# KeyMatrix.net
KiCad netlist of a schematic drawn in Altium Designer
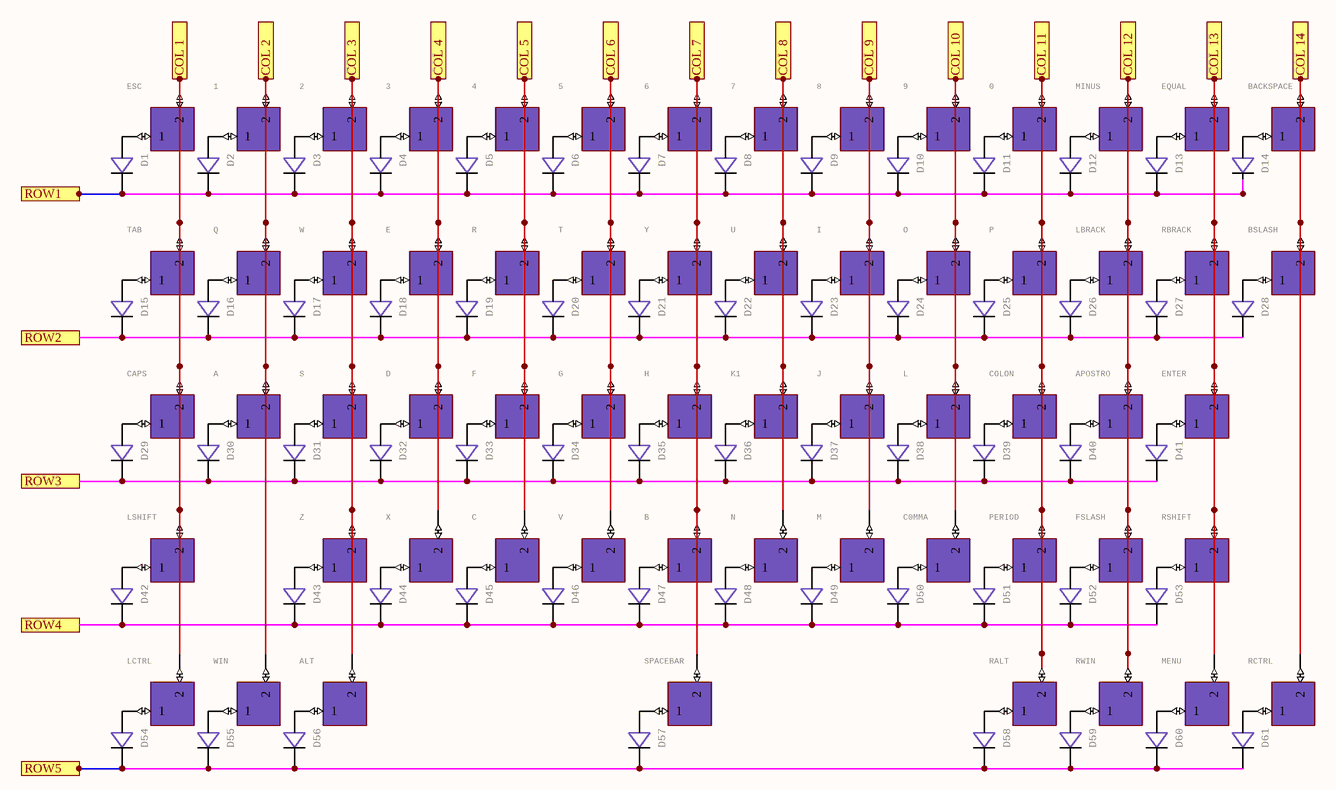
[diagram p0: KeyMatrix.SchDoc]

(export (version "E")
  (design (tool "Eeschema 10.0.6"))
  (components
    (comp (ref "0")
      (value "KEYSWITCH-PLAIN-MXHSPCB-1U")
      (footprint "MXHSPCB-1U")
      (libsource (lib "default_60") (part "KEYSWITCH-PLAIN-MXHSPCB-1U"))
    )
    (comp (ref "1")
      (value "KEYSWITCH-PLAIN-MXHSPCB-1U")
      (footprint "MXHSPCB-1U")
      (libsource (lib "default_60") (part "KEYSWITCH-PLAIN-MXHSPCB-1U"))
    )
    (comp (ref "2")
      (value "KEYSWITCH-PLAIN-MXHSPCB-1U")
      (footprint "MXHSPCB-1U")
      (libsource (lib "default_60") (part "KEYSWITCH-PLAIN-MXHSPCB-1U"))
    )
    (comp (ref "3")
      (value "KEYSWITCH-PLAIN-MXHSPCB-1U")
      (footprint "MXHSPCB-1U")
      (libsource (lib "default_60") (part "KEYSWITCH-PLAIN-MXHSPCB-1U"))
    )
    (comp (ref "4")
      (value "KEYSWITCH-PLAIN-MXHSPCB-1U")
      (footprint "MXHSPCB-1U")
      (libsource (lib "default_60") (part "KEYSWITCH-PLAIN-MXHSPCB-1U"))
    )
    (comp (ref "5")
      (value "KEYSWITCH-PLAIN-MXHSPCB-1U")
      (footprint "MXHSPCB-1U")
      (libsource (lib "default_60") (part "KEYSWITCH-PLAIN-MXHSPCB-1U"))
    )
    (comp (ref "6")
      (value "KEYSWITCH-PLAIN-MXHSPCB-1U")
      (footprint "MXHSPCB-1U")
      (libsource (lib "default_60") (part "KEYSWITCH-PLAIN-MXHSPCB-1U"))
    )
    (comp (ref "7")
      (value "KEYSWITCH-PLAIN-MXHSPCB-1U")
      (footprint "MXHSPCB-1U")
      (libsource (lib "default_60") (part "KEYSWITCH-PLAIN-MXHSPCB-1U"))
    )
    (comp (ref "8")
      (value "KEYSWITCH-PLAIN-MXHSPCB-1U")
      (footprint "MXHSPCB-1U")
      (libsource (lib "default_60") (part "KEYSWITCH-PLAIN-MXHSPCB-1U"))
    )
    (comp (ref "9")
      (value "KEYSWITCH-PLAIN-MXHSPCB-1U")
      (footprint "MXHSPCB-1U")
      (libsource (lib "default_60") (part "KEYSWITCH-PLAIN-MXHSPCB-1U"))
    )
    (comp (ref "A")
      (value "KEYSWITCH-PLAIN-MXHSPCB-1U")
      (footprint "MXHSPCB-1U")
      (libsource (lib "default_60") (part "KEYSWITCH-PLAIN-MXHSPCB-1U"))
    )
    (comp (ref "ALT")
      (value "KEYSWITCH-PLAIN-MXHSPCB-1U")
      (footprint "MXHSPCB-1U")
      (libsource (lib "default_60") (part "KEYSWITCH-PLAIN-MXHSPCB-1U"))
    )
    (comp (ref "APOSTRO")
      (value "KEYSWITCH-PLAIN-MXHSPCB-1U")
      (footprint "MXHSPCB-1U")
      (libsource (lib "default_60") (part "KEYSWITCH-PLAIN-MXHSPCB-1U"))
    )
    (comp (ref "B")
      (value "KEYSWITCH-PLAIN-MXHSPCB-1U")
      (footprint "MXHSPCB-1U")
      (libsource (lib "default_60") (part "KEYSWITCH-PLAIN-MXHSPCB-1U"))
    )
    (comp (ref "BACKSPACE")
      (value "KEYSWITCH-PLAIN-MXHSPCB-2U")
      (footprint "MXHSPCB-2U-LEDHOLE")
      (libsource (lib "default_60") (part "KEYSWITCH-PLAIN-MXHSPCB-2U"))
    )
    (comp (ref "BSLASH")
      (value "KEYSWITCH-PLAIN-MXHSPCB-1U")
      (footprint "MXHSPCB-1U")
      (libsource (lib "default_60") (part "KEYSWITCH-PLAIN-MXHSPCB-1U"))
    )
    (comp (ref "C")
      (value "KEYSWITCH-PLAIN-MXHSPCB-1U")
      (footprint "MXHSPCB-1U")
      (libsource (lib "default_60") (part "KEYSWITCH-PLAIN-MXHSPCB-1U"))
    )
    (comp (ref "C0MMA")
      (value "KEYSWITCH-PLAIN-MXHSPCB-1U")
      (footprint "MXHSPCB-1U")
      (libsource (lib "default_60") (part "KEYSWITCH-PLAIN-MXHSPCB-1U"))
    )
    (comp (ref "CAPS")
      (value "KEYSWITCH-PLAIN-MXHSPCB-1U")
      (footprint "MXHSPCB-1U")
      (libsource (lib "default_60") (part "KEYSWITCH-PLAIN-MXHSPCB-1U"))
    )
    (comp (ref "COLON")
      (value "KEYSWITCH-PLAIN-MXHSPCB-1U")
      (footprint "MXHSPCB-1U")
      (libsource (lib "default_60") (part "KEYSWITCH-PLAIN-MXHSPCB-1U"))
    )
    (comp (ref "D")
      (value "KEYSWITCH-PLAIN-MXHSPCB-1U")
      (footprint "MXHSPCB-1U")
      (libsource (lib "default_60") (part "KEYSWITCH-PLAIN-MXHSPCB-1U"))
    )
    (comp (ref "D1")
      (value "Standard 1N4148 diode")
      (footprint "SOD-123")
      (libsource (lib "default_60") (part "DIODE-SOD-123"))
    )
    (comp (ref "D2")
      (value "Standard 1N4148 diode")
      (footprint "SOD-123")
      (libsource (lib "default_60") (part "DIODE-SOD-123"))
    )
    (comp (ref "D3")
      (value "Standard 1N4148 diode")
      (footprint "SOD-123")
      (libsource (lib "default_60") (part "DIODE-SOD-123"))
    )
    (comp (ref "D4")
      (value "Standard 1N4148 diode")
      (footprint "SOD-123")
      (libsource (lib "default_60") (part "DIODE-SOD-123"))
    )
    (comp (ref "D5")
      (value "Standard 1N4148 diode")
      (footprint "SOD-123")
      (libsource (lib "default_60") (part "DIODE-SOD-123"))
    )
    (comp (ref "D6")
      (value "Standard 1N4148 diode")
      (footprint "SOD-123")
      (libsource (lib "default_60") (part "DIODE-SOD-123"))
    )
    (comp (ref "D7")
      (value "Standard 1N4148 diode")
      (footprint "SOD-123")
      (libsource (lib "default_60") (part "DIODE-SOD-123"))
    )
    (comp (ref "D8")
      (value "Standard 1N4148 diode")
      (footprint "SOD-123")
      (libsource (lib "default_60") (part "DIODE-SOD-123"))
    )
    (comp (ref "D9")
      (value "Standard 1N4148 diode")
      (footprint "SOD-123")
      (libsource (lib "default_60") (part "DIODE-SOD-123"))
    )
    (comp (ref "D10")
      (value "Standard 1N4148 diode")
      (footprint "SOD-123")
      (libsource (lib "default_60") (part "DIODE-SOD-123"))
    )
    (comp (ref "D11")
      (value "Standard 1N4148 diode")
      (footprint "SOD-123")
      (libsource (lib "default_60") (part "DIODE-SOD-123"))
    )
    (comp (ref "D12")
      (value "Standard 1N4148 diode")
      (footprint "SOD-123")
      (libsource (lib "default_60") (part "DIODE-SOD-123"))
    )
    (comp (ref "D13")
      (value "Standard 1N4148 diode")
      (footprint "SOD-123")
      (libsource (lib "default_60") (part "DIODE-SOD-123"))
    )
    (comp (ref "D14")
      (value "Standard 1N4148 diode")
      (footprint "SOD-123")
      (libsource (lib "default_60") (part "DIODE-SOD-123"))
    )
    (comp (ref "D15")
      (value "Standard 1N4148 diode")
      (footprint "SOD-123")
      (libsource (lib "default_60") (part "DIODE-SOD-123"))
    )
    (comp (ref "D16")
      (value "Standard 1N4148 diode")
      (footprint "SOD-123")
      (libsource (lib "default_60") (part "DIODE-SOD-123"))
    )
    (comp (ref "D17")
      (value "Standard 1N4148 diode")
      (footprint "SOD-123")
      (libsource (lib "default_60") (part "DIODE-SOD-123"))
    )
    (comp (ref "D18")
      (value "Standard 1N4148 diode")
      (footprint "SOD-123")
      (libsource (lib "default_60") (part "DIODE-SOD-123"))
    )
    (comp (ref "D19")
      (value "Standard 1N4148 diode")
      (footprint "SOD-123")
      (libsource (lib "default_60") (part "DIODE-SOD-123"))
    )
    (comp (ref "D20")
      (value "Standard 1N4148 diode")
      (footprint "SOD-123")
      (libsource (lib "default_60") (part "DIODE-SOD-123"))
    )
    (comp (ref "D21")
      (value "Standard 1N4148 diode")
      (footprint "SOD-123")
      (libsource (lib "default_60") (part "DIODE-SOD-123"))
    )
    (comp (ref "D22")
      (value "Standard 1N4148 diode")
      (footprint "SOD-123")
      (libsource (lib "default_60") (part "DIODE-SOD-123"))
    )
    (comp (ref "D23")
      (value "Standard 1N4148 diode")
      (footprint "SOD-123")
      (libsource (lib "default_60") (part "DIODE-SOD-123"))
    )
    (comp (ref "D24")
      (value "Standard 1N4148 diode")
      (footprint "SOD-123")
      (libsource (lib "default_60") (part "DIODE-SOD-123"))
    )
    (comp (ref "D25")
      (value "Standard 1N4148 diode")
      (footprint "SOD-123")
      (libsource (lib "default_60") (part "DIODE-SOD-123"))
    )
    (comp (ref "D26")
      (value "Standard 1N4148 diode")
      (footprint "SOD-123")
      (libsource (lib "default_60") (part "DIODE-SOD-123"))
    )
    (comp (ref "D27")
      (value "Standard 1N4148 diode")
      (footprint "SOD-123")
      (libsource (lib "default_60") (part "DIODE-SOD-123"))
    )
    (comp (ref "D28")
      (value "Standard 1N4148 diode")
      (footprint "SOD-123")
      (libsource (lib "default_60") (part "DIODE-SOD-123"))
    )
    (comp (ref "D29")
      (value "Standard 1N4148 diode")
      (footprint "SOD-123")
      (libsource (lib "default_60") (part "DIODE-SOD-123"))
    )
    (comp (ref "D30")
      (value "Standard 1N4148 diode")
      (footprint "SOD-123")
      (libsource (lib "default_60") (part "DIODE-SOD-123"))
    )
    (comp (ref "D31")
      (value "Standard 1N4148 diode")
      (footprint "SOD-123")
      (libsource (lib "default_60") (part "DIODE-SOD-123"))
    )
    (comp (ref "D32")
      (value "Standard 1N4148 diode")
      (footprint "SOD-123")
      (libsource (lib "default_60") (part "DIODE-SOD-123"))
    )
    (comp (ref "D33")
      (value "Standard 1N4148 diode")
      (footprint "SOD-123")
      (libsource (lib "default_60") (part "DIODE-SOD-123"))
    )
    (comp (ref "D34")
      (value "Standard 1N4148 diode")
      (footprint "SOD-123")
      (libsource (lib "default_60") (part "DIODE-SOD-123"))
    )
    (comp (ref "D35")
      (value "Standard 1N4148 diode")
      (footprint "SOD-123")
      (libsource (lib "default_60") (part "DIODE-SOD-123"))
    )
    (comp (ref "D36")
      (value "Standard 1N4148 diode")
      (footprint "SOD-123")
      (libsource (lib "default_60") (part "DIODE-SOD-123"))
    )
    (comp (ref "D37")
      (value "Standard 1N4148 diode")
      (footprint "SOD-123")
      (libsource (lib "default_60") (part "DIODE-SOD-123"))
    )
    (comp (ref "D38")
      (value "Standard 1N4148 diode")
      (footprint "SOD-123")
      (libsource (lib "default_60") (part "DIODE-SOD-123"))
    )
    (comp (ref "D39")
      (value "Standard 1N4148 diode")
      (footprint "SOD-123")
      (libsource (lib "default_60") (part "DIODE-SOD-123"))
    )
    (comp (ref "D40")
      (value "Standard 1N4148 diode")
      (footprint "SOD-123")
      (libsource (lib "default_60") (part "DIODE-SOD-123"))
    )
    (comp (ref "D41")
      (value "Standard 1N4148 diode")
      (footprint "SOD-123")
      (libsource (lib "default_60") (part "DIODE-SOD-123"))
    )
    (comp (ref "D42")
      (value "Standard 1N4148 diode")
      (footprint "SOD-123")
      (libsource (lib "default_60") (part "DIODE-SOD-123"))
    )
    (comp (ref "D43")
      (value "Standard 1N4148 diode")
      (footprint "SOD-123")
      (libsource (lib "default_60") (part "DIODE-SOD-123"))
    )
    (comp (ref "D44")
      (value "Standard 1N4148 diode")
      (footprint "SOD-123")
      (libsource (lib "default_60") (part "DIODE-SOD-123"))
    )
    (comp (ref "D45")
      (value "Standard 1N4148 diode")
      (footprint "SOD-123")
      (libsource (lib "default_60") (part "DIODE-SOD-123"))
    )
    (comp (ref "D46")
      (value "Standard 1N4148 diode")
      (footprint "SOD-123")
      (libsource (lib "default_60") (part "DIODE-SOD-123"))
    )
    (comp (ref "D47")
      (value "Standard 1N4148 diode")
      (footprint "SOD-123")
      (libsource (lib "default_60") (part "DIODE-SOD-123"))
    )
    (comp (ref "D48")
      (value "Standard 1N4148 diode")
      (footprint "SOD-123")
      (libsource (lib "default_60") (part "DIODE-SOD-123"))
    )
    (comp (ref "D49")
      (value "Standard 1N4148 diode")
      (footprint "SOD-123")
      (libsource (lib "default_60") (part "DIODE-SOD-123"))
    )
    (comp (ref "D50")
      (value "Standard 1N4148 diode")
      (footprint "SOD-123")
      (libsource (lib "default_60") (part "DIODE-SOD-123"))
    )
    (comp (ref "D51")
      (value "Standard 1N4148 diode")
      (footprint "SOD-123")
      (libsource (lib "default_60") (part "DIODE-SOD-123"))
    )
    (comp (ref "D52")
      (value "Standard 1N4148 diode")
      (footprint "SOD-123")
      (libsource (lib "default_60") (part "DIODE-SOD-123"))
    )
    (comp (ref "D53")
      (value "Standard 1N4148 diode")
      (footprint "SOD-123")
      (libsource (lib "default_60") (part "DIODE-SOD-123"))
    )
    (comp (ref "D54")
      (value "Standard 1N4148 diode")
      (footprint "SOD-123")
      (libsource (lib "default_60") (part "DIODE-SOD-123"))
    )
    (comp (ref "D55")
      (value "Standard 1N4148 diode")
      (footprint "SOD-123")
      (libsource (lib "default_60") (part "DIODE-SOD-123"))
    )
    (comp (ref "D56")
      (value "Standard 1N4148 diode")
      (footprint "SOD-123")
      (libsource (lib "default_60") (part "DIODE-SOD-123"))
    )
    (comp (ref "D57")
      (value "Standard 1N4148 diode")
      (footprint "SOD-123")
      (libsource (lib "default_60") (part "DIODE-SOD-123"))
    )
    (comp (ref "D58")
      (value "Standard 1N4148 diode")
      (footprint "SOD-123")
      (libsource (lib "default_60") (part "DIODE-SOD-123"))
    )
    (comp (ref "D59")
      (value "Standard 1N4148 diode")
      (footprint "SOD-123")
      (libsource (lib "default_60") (part "DIODE-SOD-123"))
    )
    (comp (ref "D60")
      (value "Standard 1N4148 diode")
      (footprint "SOD-123")
      (libsource (lib "default_60") (part "DIODE-SOD-123"))
    )
    (comp (ref "D61")
      (value "Standard 1N4148 diode")
      (footprint "SOD-123")
      (libsource (lib "default_60") (part "DIODE-SOD-123"))
    )
    (comp (ref "E")
      (value "KEYSWITCH-PLAIN-MXHSPCB-1U")
      (footprint "MXHSPCB-1U")
      (libsource (lib "default_60") (part "KEYSWITCH-PLAIN-MXHSPCB-1U"))
    )
    (comp (ref "ENTER")
      (value "KEYSWITCH-PLAIN-MXHSPCB-2U")
      (footprint "MXHSPCB-2U-LEDHOLE")
      (libsource (lib "default_60") (part "KEYSWITCH-PLAIN-MXHSPCB-2U"))
    )
    (comp (ref "EQUAL")
      (value "KEYSWITCH-PLAIN-MXHSPCB-1U")
      (footprint "MXHSPCB-1U")
      (libsource (lib "default_60") (part "KEYSWITCH-PLAIN-MXHSPCB-1U"))
    )
    (comp (ref "ESC")
      (value "KEYSWITCH-PLAIN-MXHSPCB-1U")
      (footprint "MXHSPCB-1U")
      (libsource (lib "default_60") (part "KEYSWITCH-PLAIN-MXHSPCB-1U"))
    )
    (comp (ref "F")
      (value "KEYSWITCH-PLAIN-MXHSPCB-1U")
      (footprint "MXHSPCB-1U")
      (libsource (lib "default_60") (part "KEYSWITCH-PLAIN-MXHSPCB-1U"))
    )
    (comp (ref "FSLASH")
      (value "KEYSWITCH-PLAIN-MXHSPCB-1U")
      (footprint "MXHSPCB-1U")
      (libsource (lib "default_60") (part "KEYSWITCH-PLAIN-MXHSPCB-1U"))
    )
    (comp (ref "G")
      (value "KEYSWITCH-PLAIN-MXHSPCB-1U")
      (footprint "MXHSPCB-1U")
      (libsource (lib "default_60") (part "KEYSWITCH-PLAIN-MXHSPCB-1U"))
    )
    (comp (ref "H")
      (value "KEYSWITCH-PLAIN-MXHSPCB-1U")
      (footprint "MXHSPCB-1U")
      (libsource (lib "default_60") (part "KEYSWITCH-PLAIN-MXHSPCB-1U"))
    )
    (comp (ref "I")
      (value "KEYSWITCH-PLAIN-MXHSPCB-1U")
      (footprint "MXHSPCB-1U")
      (libsource (lib "default_60") (part "KEYSWITCH-PLAIN-MXHSPCB-1U"))
    )
    (comp (ref "J")
      (value "KEYSWITCH-PLAIN-MXHSPCB-1U")
      (footprint "MXHSPCB-1U")
      (libsource (lib "default_60") (part "KEYSWITCH-PLAIN-MXHSPCB-1U"))
    )
    (comp (ref "K1")
      (value "KEYSWITCH-PLAIN-MXHSPCB-1U")
      (footprint "MXHSPCB-1U")
      (libsource (lib "default_60") (part "KEYSWITCH-PLAIN-MXHSPCB-1U"))
    )
    (comp (ref "L")
      (value "KEYSWITCH-PLAIN-MXHSPCB-1U")
      (footprint "MXHSPCB-1U")
      (libsource (lib "default_60") (part "KEYSWITCH-PLAIN-MXHSPCB-1U"))
    )
    (comp (ref "LBRACK")
      (value "KEYSWITCH-PLAIN-MXHSPCB-1U")
      (footprint "MXHSPCB-1U")
      (libsource (lib "default_60") (part "KEYSWITCH-PLAIN-MXHSPCB-1U"))
    )
    (comp (ref "LCTRL")
      (value "KEYSWITCH-PLAIN-MXHSPCB-1U")
      (footprint "MXHSPCB-1U")
      (libsource (lib "default_60") (part "KEYSWITCH-PLAIN-MXHSPCB-1U"))
    )
    (comp (ref "LSHIFT")
      (value "KEYSWITCH-PLAIN-MXHSPCB-2U")
      (footprint "MXHSPCB-2U-LEDHOLE")
      (libsource (lib "default_60") (part "KEYSWITCH-PLAIN-MXHSPCB-2U"))
    )
    (comp (ref "M")
      (value "KEYSWITCH-PLAIN-MXHSPCB-1U")
      (footprint "MXHSPCB-1U")
      (libsource (lib "default_60") (part "KEYSWITCH-PLAIN-MXHSPCB-1U"))
    )
    (comp (ref "MENU")
      (value "KEYSWITCH-PLAIN-MXHSPCB-1U")
      (footprint "MXHSPCB-1U")
      (libsource (lib "default_60") (part "KEYSWITCH-PLAIN-MXHSPCB-1U"))
    )
    (comp (ref "MINUS")
      (value "KEYSWITCH-PLAIN-MXHSPCB-1U")
      (footprint "MXHSPCB-1U")
      (libsource (lib "default_60") (part "KEYSWITCH-PLAIN-MXHSPCB-1U"))
    )
    (comp (ref "N")
      (value "KEYSWITCH-PLAIN-MXHSPCB-1U")
      (footprint "MXHSPCB-1U")
      (libsource (lib "default_60") (part "KEYSWITCH-PLAIN-MXHSPCB-1U"))
    )
    (comp (ref "O")
      (value "KEYSWITCH-PLAIN-MXHSPCB-1U")
      (footprint "MXHSPCB-1U")
      (libsource (lib "default_60") (part "KEYSWITCH-PLAIN-MXHSPCB-1U"))
    )
    (comp (ref "P")
      (value "KEYSWITCH-PLAIN-MXHSPCB-1U")
      (footprint "MXHSPCB-1U")
      (libsource (lib "default_60") (part "KEYSWITCH-PLAIN-MXHSPCB-1U"))
    )
    (comp (ref "PERIOD")
      (value "KEYSWITCH-PLAIN-MXHSPCB-1U")
      (footprint "MXHSPCB-1U")
      (libsource (lib "default_60") (part "KEYSWITCH-PLAIN-MXHSPCB-1U"))
    )
    (comp (ref "Q")
      (value "KEYSWITCH-PLAIN-MXHSPCB-1U")
      (footprint "MXHSPCB-1U")
      (libsource (lib "default_60") (part "KEYSWITCH-PLAIN-MXHSPCB-1U"))
    )
    (comp (ref "R")
      (value "KEYSWITCH-PLAIN-MXHSPCB-1U")
      (footprint "MXHSPCB-1U")
      (libsource (lib "default_60") (part "KEYSWITCH-PLAIN-MXHSPCB-1U"))
    )
    (comp (ref "RALT")
      (value "KEYSWITCH-PLAIN-MXHSPCB-1U")
      (footprint "MXHSPCB-1U")
      (libsource (lib "default_60") (part "KEYSWITCH-PLAIN-MXHSPCB-1U"))
    )
    (comp (ref "RBRACK")
      (value "KEYSWITCH-PLAIN-MXHSPCB-1U")
      (footprint "MXHSPCB-1U")
      (libsource (lib "default_60") (part "KEYSWITCH-PLAIN-MXHSPCB-1U"))
    )
    (comp (ref "RCTRL")
      (value "KEYSWITCH-PLAIN-MXHSPCB-1U")
      (footprint "MXHSPCB-1U")
      (libsource (lib "default_60") (part "KEYSWITCH-PLAIN-MXHSPCB-1U"))
    )
    (comp (ref "RSHIFT")
      (value "KEYSWITCH-PLAIN-MXHSPCB-2U")
      (footprint "MXHSPCB-2U-LEDHOLE")
      (libsource (lib "default_60") (part "KEYSWITCH-PLAIN-MXHSPCB-2U"))
    )
    (comp (ref "RWIN")
      (value "KEYSWITCH-PLAIN-MXHSPCB-1U")
      (footprint "MXHSPCB-1U")
      (libsource (lib "default_60") (part "KEYSWITCH-PLAIN-MXHSPCB-1U"))
    )
    (comp (ref "S")
      (value "KEYSWITCH-PLAIN-MXHSPCB-1U")
      (footprint "MXHSPCB-1U")
      (libsource (lib "default_60") (part "KEYSWITCH-PLAIN-MXHSPCB-1U"))
    )
    (comp (ref "SPACEBAR")
      (value "KEYSWITCH-PLAIN-MXHSPCB-6.25U")
      (footprint "MXHSPCB-6.25U-FLIPPED")
      (libsource (lib "default_60") (part "KEYSWITCH-PLAIN-MXHSPCB-6.25U"))
    )
    (comp (ref "T")
      (value "KEYSWITCH-PLAIN-MXHSPCB-1U")
      (footprint "MXHSPCB-1U")
      (libsource (lib "default_60") (part "KEYSWITCH-PLAIN-MXHSPCB-1U"))
    )
    (comp (ref "TAB")
      (value "KEYSWITCH-PLAIN-MXHSPCB-1U")
      (footprint "MXHSPCB-1U")
      (libsource (lib "default_60") (part "KEYSWITCH-PLAIN-MXHSPCB-1U"))
    )
    (comp (ref "U")
      (value "KEYSWITCH-PLAIN-MXHSPCB-1U")
      (footprint "MXHSPCB-1U")
      (libsource (lib "default_60") (part "KEYSWITCH-PLAIN-MXHSPCB-1U"))
    )
    (comp (ref "V")
      (value "KEYSWITCH-PLAIN-MXHSPCB-1U")
      (footprint "MXHSPCB-1U")
      (libsource (lib "default_60") (part "KEYSWITCH-PLAIN-MXHSPCB-1U"))
    )
    (comp (ref "W")
      (value "KEYSWITCH-PLAIN-MXHSPCB-1U")
      (footprint "MXHSPCB-1U")
      (libsource (lib "default_60") (part "KEYSWITCH-PLAIN-MXHSPCB-1U"))
    )
    (comp (ref "WIN")
      (value "KEYSWITCH-PLAIN-MXHSPCB-1U")
      (footprint "MXHSPCB-1U")
      (libsource (lib "default_60") (part "KEYSWITCH-PLAIN-MXHSPCB-1U"))
    )
    (comp (ref "X")
      (value "KEYSWITCH-PLAIN-MXHSPCB-1U")
      (footprint "MXHSPCB-1U")
      (libsource (lib "default_60") (part "KEYSWITCH-PLAIN-MXHSPCB-1U"))
    )
    (comp (ref "Y")
      (value "KEYSWITCH-PLAIN-MXHSPCB-1U")
      (footprint "MXHSPCB-1U")
      (libsource (lib "default_60") (part "KEYSWITCH-PLAIN-MXHSPCB-1U"))
    )
    (comp (ref "Z")
      (value "KEYSWITCH-PLAIN-MXHSPCB-1U")
      (footprint "MXHSPCB-1U")
      (libsource (lib "default_60") (part "KEYSWITCH-PLAIN-MXHSPCB-1U"))
    )
  )
  (nets
    (net (code "1") (name "/COL 1") (class "Default")
      (node (ref "CAPS") (pin "MX2") (pinfunction "2_MX2") (pintype "bidirectional"))
      (node (ref "ESC") (pin "MX2") (pinfunction "2_MX2") (pintype "bidirectional"))
      (node (ref "LCTRL") (pin "MX2") (pinfunction "2_MX2") (pintype "bidirectional"))
      (node (ref "LSHIFT") (pin "MX2") (pinfunction "2_MX2") (pintype "bidirectional"))
      (node (ref "TAB") (pin "MX2") (pinfunction "2_MX2") (pintype "bidirectional"))
    )
    (net (code "2") (name "/COL 2") (class "Default")
      (node (ref "1") (pin "MX2") (pinfunction "2_MX2") (pintype "bidirectional"))
      (node (ref "A") (pin "MX2") (pinfunction "2_MX2") (pintype "bidirectional"))
      (node (ref "Q") (pin "MX2") (pinfunction "2_MX2") (pintype "bidirectional"))
      (node (ref "WIN") (pin "MX2") (pinfunction "2_MX2") (pintype "bidirectional"))
    )
    (net (code "3") (name "/COL 3") (class "Default")
      (node (ref "2") (pin "MX2") (pinfunction "2_MX2") (pintype "bidirectional"))
      (node (ref "ALT") (pin "MX2") (pinfunction "2_MX2") (pintype "bidirectional"))
      (node (ref "S") (pin "MX2") (pinfunction "2_MX2") (pintype "bidirectional"))
      (node (ref "W") (pin "MX2") (pinfunction "2_MX2") (pintype "bidirectional"))
      (node (ref "Z") (pin "MX2") (pinfunction "2_MX2") (pintype "bidirectional"))
    )
    (net (code "4") (name "/COL 4") (class "Default")
      (node (ref "3") (pin "MX2") (pinfunction "2_MX2") (pintype "bidirectional"))
      (node (ref "D") (pin "MX2") (pinfunction "2_MX2") (pintype "bidirectional"))
      (node (ref "E") (pin "MX2") (pinfunction "2_MX2") (pintype "bidirectional"))
      (node (ref "X") (pin "MX2") (pinfunction "2_MX2") (pintype "bidirectional"))
    )
    (net (code "5") (name "/COL 5") (class "Default")
      (node (ref "4") (pin "MX2") (pinfunction "2_MX2") (pintype "bidirectional"))
      (node (ref "C") (pin "MX2") (pinfunction "2_MX2") (pintype "bidirectional"))
      (node (ref "F") (pin "MX2") (pinfunction "2_MX2") (pintype "bidirectional"))
      (node (ref "R") (pin "MX2") (pinfunction "2_MX2") (pintype "bidirectional"))
    )
    (net (code "6") (name "/COL 6") (class "Default")
      (node (ref "5") (pin "MX2") (pinfunction "2_MX2") (pintype "bidirectional"))
      (node (ref "G") (pin "MX2") (pinfunction "2_MX2") (pintype "bidirectional"))
      (node (ref "T") (pin "MX2") (pinfunction "2_MX2") (pintype "bidirectional"))
      (node (ref "V") (pin "MX2") (pinfunction "2_MX2") (pintype "bidirectional"))
    )
    (net (code "7") (name "/COL 7") (class "Default")
      (node (ref "6") (pin "MX2") (pinfunction "2_MX2") (pintype "bidirectional"))
      (node (ref "B") (pin "MX2") (pinfunction "2_MX2") (pintype "bidirectional"))
      (node (ref "H") (pin "MX2") (pinfunction "2_MX2") (pintype "bidirectional"))
      (node (ref "SPACEBAR") (pin "MX2") (pinfunction "2_MX2") (pintype "bidirectional"))
      (node (ref "Y") (pin "MX2") (pinfunction "2_MX2") (pintype "bidirectional"))
    )
    (net (code "8") (name "/COL 8") (class "Default")
      (node (ref "7") (pin "MX2") (pinfunction "2_MX2") (pintype "bidirectional"))
      (node (ref "K1") (pin "MX2") (pinfunction "2_MX2") (pintype "bidirectional"))
      (node (ref "N") (pin "MX2") (pinfunction "2_MX2") (pintype "bidirectional"))
      (node (ref "U") (pin "MX2") (pinfunction "2_MX2") (pintype "bidirectional"))
    )
    (net (code "9") (name "/COL 9") (class "Default")
      (node (ref "8") (pin "MX2") (pinfunction "2_MX2") (pintype "bidirectional"))
      (node (ref "I") (pin "MX2") (pinfunction "2_MX2") (pintype "bidirectional"))
      (node (ref "J") (pin "MX2") (pinfunction "2_MX2") (pintype "bidirectional"))
      (node (ref "M") (pin "MX2") (pinfunction "2_MX2") (pintype "bidirectional"))
    )
    (net (code "10") (name "/COL 10") (class "Default")
      (node (ref "9") (pin "MX2") (pinfunction "2_MX2") (pintype "bidirectional"))
      (node (ref "C0MMA") (pin "MX2") (pinfunction "2_MX2") (pintype "bidirectional"))
      (node (ref "L") (pin "MX2") (pinfunction "2_MX2") (pintype "bidirectional"))
      (node (ref "O") (pin "MX2") (pinfunction "2_MX2") (pintype "bidirectional"))
    )
    (net (code "11") (name "/COL 11") (class "Default")
      (node (ref "0") (pin "MX2") (pinfunction "2_MX2") (pintype "bidirectional"))
      (node (ref "COLON") (pin "MX2") (pinfunction "2_MX2") (pintype "bidirectional"))
      (node (ref "P") (pin "MX2") (pinfunction "2_MX2") (pintype "bidirectional"))
      (node (ref "PERIOD") (pin "MX2") (pinfunction "2_MX2") (pintype "bidirectional"))
      (node (ref "RALT") (pin "MX2") (pinfunction "2_MX2") (pintype "bidirectional"))
    )
    (net (code "12") (name "/COL 12") (class "Default")
      (node (ref "APOSTRO") (pin "MX2") (pinfunction "2_MX2") (pintype "bidirectional"))
      (node (ref "FSLASH") (pin "MX2") (pinfunction "2_MX2") (pintype "bidirectional"))
      (node (ref "LBRACK") (pin "MX2") (pinfunction "2_MX2") (pintype "bidirectional"))
      (node (ref "MINUS") (pin "MX2") (pinfunction "2_MX2") (pintype "bidirectional"))
      (node (ref "RWIN") (pin "MX2") (pinfunction "2_MX2") (pintype "bidirectional"))
    )
    (net (code "13") (name "/COL 13") (class "Default")
      (node (ref "ENTER") (pin "MX2") (pinfunction "2_MX2") (pintype "bidirectional"))
      (node (ref "EQUAL") (pin "MX2") (pinfunction "2_MX2") (pintype "bidirectional"))
      (node (ref "MENU") (pin "MX2") (pinfunction "2_MX2") (pintype "bidirectional"))
      (node (ref "RBRACK") (pin "MX2") (pinfunction "2_MX2") (pintype "bidirectional"))
      (node (ref "RSHIFT") (pin "MX2") (pinfunction "2_MX2") (pintype "bidirectional"))
    )
    (net (code "14") (name "/COL 14") (class "Default")
      (node (ref "BACKSPACE") (pin "MX2") (pinfunction "2_MX2") (pintype "bidirectional"))
      (node (ref "BSLASH") (pin "MX2") (pinfunction "2_MX2") (pintype "bidirectional"))
      (node (ref "RCTRL") (pin "MX2") (pinfunction "2_MX2") (pintype "bidirectional"))
    )
    (net (code "15") (name "/ROW1") (class "Default")
      (node (ref "D1") (pin "C") (pinfunction "C_C") (pintype "passive"))
      (node (ref "D10") (pin "C") (pinfunction "C_C") (pintype "passive"))
      (node (ref "D11") (pin "C") (pinfunction "C_C") (pintype "passive"))
      (node (ref "D12") (pin "C") (pinfunction "C_C") (pintype "passive"))
      (node (ref "D13") (pin "C") (pinfunction "C_C") (pintype "passive"))
      (node (ref "D14") (pin "C") (pinfunction "C_C") (pintype "passive"))
      (node (ref "D2") (pin "C") (pinfunction "C_C") (pintype "passive"))
      (node (ref "D3") (pin "C") (pinfunction "C_C") (pintype "passive"))
      (node (ref "D4") (pin "C") (pinfunction "C_C") (pintype "passive"))
      (node (ref "D5") (pin "C") (pinfunction "C_C") (pintype "passive"))
      (node (ref "D6") (pin "C") (pinfunction "C_C") (pintype "passive"))
      (node (ref "D7") (pin "C") (pinfunction "C_C") (pintype "passive"))
      (node (ref "D8") (pin "C") (pinfunction "C_C") (pintype "passive"))
      (node (ref "D9") (pin "C") (pinfunction "C_C") (pintype "passive"))
    )
    (net (code "16") (name "/ROW2") (class "Default")
      (node (ref "D15") (pin "C") (pinfunction "C_C") (pintype "passive"))
      (node (ref "D16") (pin "C") (pinfunction "C_C") (pintype "passive"))
      (node (ref "D17") (pin "C") (pinfunction "C_C") (pintype "passive"))
      (node (ref "D18") (pin "C") (pinfunction "C_C") (pintype "passive"))
      (node (ref "D19") (pin "C") (pinfunction "C_C") (pintype "passive"))
      (node (ref "D20") (pin "C") (pinfunction "C_C") (pintype "passive"))
      (node (ref "D21") (pin "C") (pinfunction "C_C") (pintype "passive"))
      (node (ref "D22") (pin "C") (pinfunction "C_C") (pintype "passive"))
      (node (ref "D23") (pin "C") (pinfunction "C_C") (pintype "passive"))
      (node (ref "D24") (pin "C") (pinfunction "C_C") (pintype "passive"))
      (node (ref "D25") (pin "C") (pinfunction "C_C") (pintype "passive"))
      (node (ref "D26") (pin "C") (pinfunction "C_C") (pintype "passive"))
      (node (ref "D27") (pin "C") (pinfunction "C_C") (pintype "passive"))
      (node (ref "D28") (pin "C") (pinfunction "C_C") (pintype "passive"))
    )
    (net (code "17") (name "/ROW3") (class "Default")
      (node (ref "D29") (pin "C") (pinfunction "C_C") (pintype "passive"))
      (node (ref "D30") (pin "C") (pinfunction "C_C") (pintype "passive"))
      (node (ref "D31") (pin "C") (pinfunction "C_C") (pintype "passive"))
      (node (ref "D32") (pin "C") (pinfunction "C_C") (pintype "passive"))
      (node (ref "D33") (pin "C") (pinfunction "C_C") (pintype "passive"))
      (node (ref "D34") (pin "C") (pinfunction "C_C") (pintype "passive"))
      (node (ref "D35") (pin "C") (pinfunction "C_C") (pintype "passive"))
      (node (ref "D36") (pin "C") (pinfunction "C_C") (pintype "passive"))
      (node (ref "D37") (pin "C") (pinfunction "C_C") (pintype "passive"))
      (node (ref "D38") (pin "C") (pinfunction "C_C") (pintype "passive"))
      (node (ref "D39") (pin "C") (pinfunction "C_C") (pintype "passive"))
      (node (ref "D40") (pin "C") (pinfunction "C_C") (pintype "passive"))
      (node (ref "D41") (pin "C") (pinfunction "C_C") (pintype "passive"))
    )
    (net (code "18") (name "/ROW4") (class "Default")
      (node (ref "D42") (pin "C") (pinfunction "C_C") (pintype "passive"))
      (node (ref "D43") (pin "C") (pinfunction "C_C") (pintype "passive"))
      (node (ref "D44") (pin "C") (pinfunction "C_C") (pintype "passive"))
      (node (ref "D45") (pin "C") (pinfunction "C_C") (pintype "passive"))
      (node (ref "D46") (pin "C") (pinfunction "C_C") (pintype "passive"))
      (node (ref "D47") (pin "C") (pinfunction "C_C") (pintype "passive"))
      (node (ref "D48") (pin "C") (pinfunction "C_C") (pintype "passive"))
      (node (ref "D49") (pin "C") (pinfunction "C_C") (pintype "passive"))
      (node (ref "D50") (pin "C") (pinfunction "C_C") (pintype "passive"))
      (node (ref "D51") (pin "C") (pinfunction "C_C") (pintype "passive"))
      (node (ref "D52") (pin "C") (pinfunction "C_C") (pintype "passive"))
      (node (ref "D53") (pin "C") (pinfunction "C_C") (pintype "passive"))
    )
    (net (code "19") (name "/ROW5") (class "Default")
      (node (ref "D54") (pin "C") (pinfunction "C_C") (pintype "passive"))
      (node (ref "D55") (pin "C") (pinfunction "C_C") (pintype "passive"))
      (node (ref "D56") (pin "C") (pinfunction "C_C") (pintype "passive"))
      (node (ref "D57") (pin "C") (pinfunction "C_C") (pintype "passive"))
      (node (ref "D58") (pin "C") (pinfunction "C_C") (pintype "passive"))
      (node (ref "D59") (pin "C") (pinfunction "C_C") (pintype "passive"))
      (node (ref "D60") (pin "C") (pinfunction "C_C") (pintype "passive"))
      (node (ref "D61") (pin "C") (pinfunction "C_C") (pintype "passive"))
    )
    (net (code "20") (name "Net-(0-1)") (class "Default")
      (node (ref "0") (pin "MX1") (pinfunction "1_MX1") (pintype "bidirectional"))
      (node (ref "D11") (pin "A") (pinfunction "A_A") (pintype "passive"))
    )
    (net (code "21") (name "Net-(1-1)") (class "Default")
      (node (ref "1") (pin "MX1") (pinfunction "1_MX1") (pintype "bidirectional"))
      (node (ref "D2") (pin "A") (pinfunction "A_A") (pintype "passive"))
    )
    (net (code "22") (name "Net-(2-1)") (class "Default")
      (node (ref "2") (pin "MX1") (pinfunction "1_MX1") (pintype "bidirectional"))
      (node (ref "D3") (pin "A") (pinfunction "A_A") (pintype "passive"))
    )
    (net (code "23") (name "Net-(3-1)") (class "Default")
      (node (ref "3") (pin "MX1") (pinfunction "1_MX1") (pintype "bidirectional"))
      (node (ref "D4") (pin "A") (pinfunction "A_A") (pintype "passive"))
    )
    (net (code "24") (name "Net-(4-1)") (class "Default")
      (node (ref "4") (pin "MX1") (pinfunction "1_MX1") (pintype "bidirectional"))
      (node (ref "D5") (pin "A") (pinfunction "A_A") (pintype "passive"))
    )
    (net (code "25") (name "Net-(5-1)") (class "Default")
      (node (ref "5") (pin "MX1") (pinfunction "1_MX1") (pintype "bidirectional"))
      (node (ref "D6") (pin "A") (pinfunction "A_A") (pintype "passive"))
    )
    (net (code "26") (name "Net-(6-1)") (class "Default")
      (node (ref "6") (pin "MX1") (pinfunction "1_MX1") (pintype "bidirectional"))
      (node (ref "D7") (pin "A") (pinfunction "A_A") (pintype "passive"))
    )
    (net (code "27") (name "Net-(7-1)") (class "Default")
      (node (ref "7") (pin "MX1") (pinfunction "1_MX1") (pintype "bidirectional"))
      (node (ref "D8") (pin "A") (pinfunction "A_A") (pintype "passive"))
    )
    (net (code "28") (name "Net-(8-1)") (class "Default")
      (node (ref "8") (pin "MX1") (pinfunction "1_MX1") (pintype "bidirectional"))
      (node (ref "D9") (pin "A") (pinfunction "A_A") (pintype "passive"))
    )
    (net (code "29") (name "Net-(9-1)") (class "Default")
      (node (ref "9") (pin "MX1") (pinfunction "1_MX1") (pintype "bidirectional"))
      (node (ref "D10") (pin "A") (pinfunction "A_A") (pintype "passive"))
    )
    (net (code "30") (name "Net-(A-1)") (class "Default")
      (node (ref "A") (pin "MX1") (pinfunction "1_MX1") (pintype "bidirectional"))
      (node (ref "D30") (pin "A") (pinfunction "A_A") (pintype "passive"))
    )
    (net (code "31") (name "Net-(ALT-1)") (class "Default")
      (node (ref "ALT") (pin "MX1") (pinfunction "1_MX1") (pintype "bidirectional"))
      (node (ref "D56") (pin "A") (pinfunction "A_A") (pintype "passive"))
    )
    (net (code "32") (name "Net-(APOSTRO-1)") (class "Default")
      (node (ref "APOSTRO") (pin "MX1") (pinfunction "1_MX1") (pintype "bidirectional"))
      (node (ref "D40") (pin "A") (pinfunction "A_A") (pintype "passive"))
    )
    (net (code "33") (name "Net-(B-1)") (class "Default")
      (node (ref "B") (pin "MX1") (pinfunction "1_MX1") (pintype "bidirectional"))
      (node (ref "D47") (pin "A") (pinfunction "A_A") (pintype "passive"))
    )
    (net (code "34") (name "Net-(BACKSPACE-1)") (class "Default")
      (node (ref "BACKSPACE") (pin "MX1") (pinfunction "1_MX1") (pintype "bidirectional"))
      (node (ref "D14") (pin "A") (pinfunction "A_A") (pintype "passive"))
    )
    (net (code "35") (name "Net-(BSLASH-1)") (class "Default")
      (node (ref "BSLASH") (pin "MX1") (pinfunction "1_MX1") (pintype "bidirectional"))
      (node (ref "D28") (pin "A") (pinfunction "A_A") (pintype "passive"))
    )
    (net (code "36") (name "Net-(C-1)") (class "Default")
      (node (ref "C") (pin "MX1") (pinfunction "1_MX1") (pintype "bidirectional"))
      (node (ref "D45") (pin "A") (pinfunction "A_A") (pintype "passive"))
    )
    (net (code "37") (name "Net-(C0MMA-1)") (class "Default")
      (node (ref "C0MMA") (pin "MX1") (pinfunction "1_MX1") (pintype "bidirectional"))
      (node (ref "D50") (pin "A") (pinfunction "A_A") (pintype "passive"))
    )
    (net (code "38") (name "Net-(CAPS-1)") (class "Default")
      (node (ref "CAPS") (pin "MX1") (pinfunction "1_MX1") (pintype "bidirectional"))
      (node (ref "D29") (pin "A") (pinfunction "A_A") (pintype "passive"))
    )
    (net (code "39") (name "Net-(COLON-1)") (class "Default")
      (node (ref "COLON") (pin "MX1") (pinfunction "1_MX1") (pintype "bidirectional"))
      (node (ref "D39") (pin "A") (pinfunction "A_A") (pintype "passive"))
    )
    (net (code "40") (name "Net-(D-1)") (class "Default")
      (node (ref "D") (pin "MX1") (pinfunction "1_MX1") (pintype "bidirectional"))
      (node (ref "D32") (pin "A") (pinfunction "A_A") (pintype "passive"))
    )
    (net (code "41") (name "Net-(E-1)") (class "Default")
      (node (ref "D18") (pin "A") (pinfunction "A_A") (pintype "passive"))
      (node (ref "E") (pin "MX1") (pinfunction "1_MX1") (pintype "bidirectional"))
    )
    (net (code "42") (name "Net-(ENTER-1)") (class "Default")
      (node (ref "D41") (pin "A") (pinfunction "A_A") (pintype "passive"))
      (node (ref "ENTER") (pin "MX1") (pinfunction "1_MX1") (pintype "bidirectional"))
    )
    (net (code "43") (name "Net-(EQUAL-1)") (class "Default")
      (node (ref "D13") (pin "A") (pinfunction "A_A") (pintype "passive"))
      (node (ref "EQUAL") (pin "MX1") (pinfunction "1_MX1") (pintype "bidirectional"))
    )
    (net (code "44") (name "Net-(ESC-1)") (class "Default")
      (node (ref "D1") (pin "A") (pinfunction "A_A") (pintype "passive"))
      (node (ref "ESC") (pin "MX1") (pinfunction "1_MX1") (pintype "bidirectional"))
    )
    (net (code "45") (name "Net-(F-1)") (class "Default")
      (node (ref "D33") (pin "A") (pinfunction "A_A") (pintype "passive"))
      (node (ref "F") (pin "MX1") (pinfunction "1_MX1") (pintype "bidirectional"))
    )
    (net (code "46") (name "Net-(FSLASH-1)") (class "Default")
      (node (ref "D52") (pin "A") (pinfunction "A_A") (pintype "passive"))
      (node (ref "FSLASH") (pin "MX1") (pinfunction "1_MX1") (pintype "bidirectional"))
    )
    (net (code "47") (name "Net-(G-1)") (class "Default")
      (node (ref "D34") (pin "A") (pinfunction "A_A") (pintype "passive"))
      (node (ref "G") (pin "MX1") (pinfunction "1_MX1") (pintype "bidirectional"))
    )
    (net (code "48") (name "Net-(H-1)") (class "Default")
      (node (ref "D35") (pin "A") (pinfunction "A_A") (pintype "passive"))
      (node (ref "H") (pin "MX1") (pinfunction "1_MX1") (pintype "bidirectional"))
    )
    (net (code "49") (name "Net-(I-1)") (class "Default")
      (node (ref "D23") (pin "A") (pinfunction "A_A") (pintype "passive"))
      (node (ref "I") (pin "MX1") (pinfunction "1_MX1") (pintype "bidirectional"))
    )
    (net (code "50") (name "Net-(J-1)") (class "Default")
      (node (ref "D37") (pin "A") (pinfunction "A_A") (pintype "passive"))
      (node (ref "J") (pin "MX1") (pinfunction "1_MX1") (pintype "bidirectional"))
    )
    (net (code "51") (name "Net-(K1-1)") (class "Default")
      (node (ref "D36") (pin "A") (pinfunction "A_A") (pintype "passive"))
      (node (ref "K1") (pin "MX1") (pinfunction "1_MX1") (pintype "bidirectional"))
    )
    (net (code "52") (name "Net-(L-1)") (class "Default")
      (node (ref "D38") (pin "A") (pinfunction "A_A") (pintype "passive"))
      (node (ref "L") (pin "MX1") (pinfunction "1_MX1") (pintype "bidirectional"))
    )
    (net (code "53") (name "Net-(LBRACK-1)") (class "Default")
      (node (ref "D26") (pin "A") (pinfunction "A_A") (pintype "passive"))
      (node (ref "LBRACK") (pin "MX1") (pinfunction "1_MX1") (pintype "bidirectional"))
    )
    (net (code "54") (name "Net-(LCTRL-1)") (class "Default")
      (node (ref "D54") (pin "A") (pinfunction "A_A") (pintype "passive"))
      (node (ref "LCTRL") (pin "MX1") (pinfunction "1_MX1") (pintype "bidirectional"))
    )
    (net (code "55") (name "Net-(LSHIFT-1)") (class "Default")
      (node (ref "D42") (pin "A") (pinfunction "A_A") (pintype "passive"))
      (node (ref "LSHIFT") (pin "MX1") (pinfunction "1_MX1") (pintype "bidirectional"))
    )
    (net (code "56") (name "Net-(M-1)") (class "Default")
      (node (ref "D49") (pin "A") (pinfunction "A_A") (pintype "passive"))
      (node (ref "M") (pin "MX1") (pinfunction "1_MX1") (pintype "bidirectional"))
    )
    (net (code "57") (name "Net-(MENU-1)") (class "Default")
      (node (ref "D60") (pin "A") (pinfunction "A_A") (pintype "passive"))
      (node (ref "MENU") (pin "MX1") (pinfunction "1_MX1") (pintype "bidirectional"))
    )
    (net (code "58") (name "Net-(MINUS-1)") (class "Default")
      (node (ref "D12") (pin "A") (pinfunction "A_A") (pintype "passive"))
      (node (ref "MINUS") (pin "MX1") (pinfunction "1_MX1") (pintype "bidirectional"))
    )
    (net (code "59") (name "Net-(N-1)") (class "Default")
      (node (ref "D48") (pin "A") (pinfunction "A_A") (pintype "passive"))
      (node (ref "N") (pin "MX1") (pinfunction "1_MX1") (pintype "bidirectional"))
    )
    (net (code "60") (name "Net-(O-1)") (class "Default")
      (node (ref "D24") (pin "A") (pinfunction "A_A") (pintype "passive"))
      (node (ref "O") (pin "MX1") (pinfunction "1_MX1") (pintype "bidirectional"))
    )
    (net (code "61") (name "Net-(P-1)") (class "Default")
      (node (ref "D25") (pin "A") (pinfunction "A_A") (pintype "passive"))
      (node (ref "P") (pin "MX1") (pinfunction "1_MX1") (pintype "bidirectional"))
    )
    (net (code "62") (name "Net-(PERIOD-1)") (class "Default")
      (node (ref "D51") (pin "A") (pinfunction "A_A") (pintype "passive"))
      (node (ref "PERIOD") (pin "MX1") (pinfunction "1_MX1") (pintype "bidirectional"))
    )
    (net (code "63") (name "Net-(Q-1)") (class "Default")
      (node (ref "D16") (pin "A") (pinfunction "A_A") (pintype "passive"))
      (node (ref "Q") (pin "MX1") (pinfunction "1_MX1") (pintype "bidirectional"))
    )
    (net (code "64") (name "Net-(R-1)") (class "Default")
      (node (ref "D19") (pin "A") (pinfunction "A_A") (pintype "passive"))
      (node (ref "R") (pin "MX1") (pinfunction "1_MX1") (pintype "bidirectional"))
    )
    (net (code "65") (name "Net-(RALT-1)") (class "Default")
      (node (ref "D58") (pin "A") (pinfunction "A_A") (pintype "passive"))
      (node (ref "RALT") (pin "MX1") (pinfunction "1_MX1") (pintype "bidirectional"))
    )
    (net (code "66") (name "Net-(RBRACK-1)") (class "Default")
      (node (ref "D27") (pin "A") (pinfunction "A_A") (pintype "passive"))
      (node (ref "RBRACK") (pin "MX1") (pinfunction "1_MX1") (pintype "bidirectional"))
    )
    (net (code "67") (name "Net-(RCTRL-1)") (class "Default")
      (node (ref "D61") (pin "A") (pinfunction "A_A") (pintype "passive"))
      (node (ref "RCTRL") (pin "MX1") (pinfunction "1_MX1") (pintype "bidirectional"))
    )
    (net (code "68") (name "Net-(RSHIFT-1)") (class "Default")
      (node (ref "D53") (pin "A") (pinfunction "A_A") (pintype "passive"))
      (node (ref "RSHIFT") (pin "MX1") (pinfunction "1_MX1") (pintype "bidirectional"))
    )
    (net (code "69") (name "Net-(RWIN-1)") (class "Default")
      (node (ref "D59") (pin "A") (pinfunction "A_A") (pintype "passive"))
      (node (ref "RWIN") (pin "MX1") (pinfunction "1_MX1") (pintype "bidirectional"))
    )
    (net (code "70") (name "Net-(S-1)") (class "Default")
      (node (ref "D31") (pin "A") (pinfunction "A_A") (pintype "passive"))
      (node (ref "S") (pin "MX1") (pinfunction "1_MX1") (pintype "bidirectional"))
    )
    (net (code "71") (name "Net-(SPACEBAR-1)") (class "Default")
      (node (ref "D57") (pin "A") (pinfunction "A_A") (pintype "passive"))
      (node (ref "SPACEBAR") (pin "MX1") (pinfunction "1_MX1") (pintype "bidirectional"))
    )
    (net (code "72") (name "Net-(T-1)") (class "Default")
      (node (ref "D20") (pin "A") (pinfunction "A_A") (pintype "passive"))
      (node (ref "T") (pin "MX1") (pinfunction "1_MX1") (pintype "bidirectional"))
    )
    (net (code "73") (name "Net-(TAB-1)") (class "Default")
      (node (ref "D15") (pin "A") (pinfunction "A_A") (pintype "passive"))
      (node (ref "TAB") (pin "MX1") (pinfunction "1_MX1") (pintype "bidirectional"))
    )
    (net (code "74") (name "Net-(U-1)") (class "Default")
      (node (ref "D22") (pin "A") (pinfunction "A_A") (pintype "passive"))
      (node (ref "U") (pin "MX1") (pinfunction "1_MX1") (pintype "bidirectional"))
    )
    (net (code "75") (name "Net-(V-1)") (class "Default")
      (node (ref "D46") (pin "A") (pinfunction "A_A") (pintype "passive"))
      (node (ref "V") (pin "MX1") (pinfunction "1_MX1") (pintype "bidirectional"))
    )
    (net (code "76") (name "Net-(W-1)") (class "Default")
      (node (ref "D17") (pin "A") (pinfunction "A_A") (pintype "passive"))
      (node (ref "W") (pin "MX1") (pinfunction "1_MX1") (pintype "bidirectional"))
    )
    (net (code "77") (name "Net-(WIN-1)") (class "Default")
      (node (ref "D55") (pin "A") (pinfunction "A_A") (pintype "passive"))
      (node (ref "WIN") (pin "MX1") (pinfunction "1_MX1") (pintype "bidirectional"))
    )
    (net (code "78") (name "Net-(X-1)") (class "Default")
      (node (ref "D44") (pin "A") (pinfunction "A_A") (pintype "passive"))
      (node (ref "X") (pin "MX1") (pinfunction "1_MX1") (pintype "bidirectional"))
    )
    (net (code "79") (name "Net-(Y-1)") (class "Default")
      (node (ref "D21") (pin "A") (pinfunction "A_A") (pintype "passive"))
      (node (ref "Y") (pin "MX1") (pinfunction "1_MX1") (pintype "bidirectional"))
    )
    (net (code "80") (name "Net-(Z-1)") (class "Default")
      (node (ref "D43") (pin "A") (pinfunction "A_A") (pintype "passive"))
      (node (ref "Z") (pin "MX1") (pinfunction "1_MX1") (pintype "bidirectional"))
    )
  )
)
